# TriggerTrap_MainBoard_0v39_Release.net
KiCad netlist of a schematic drawn in EAGLE
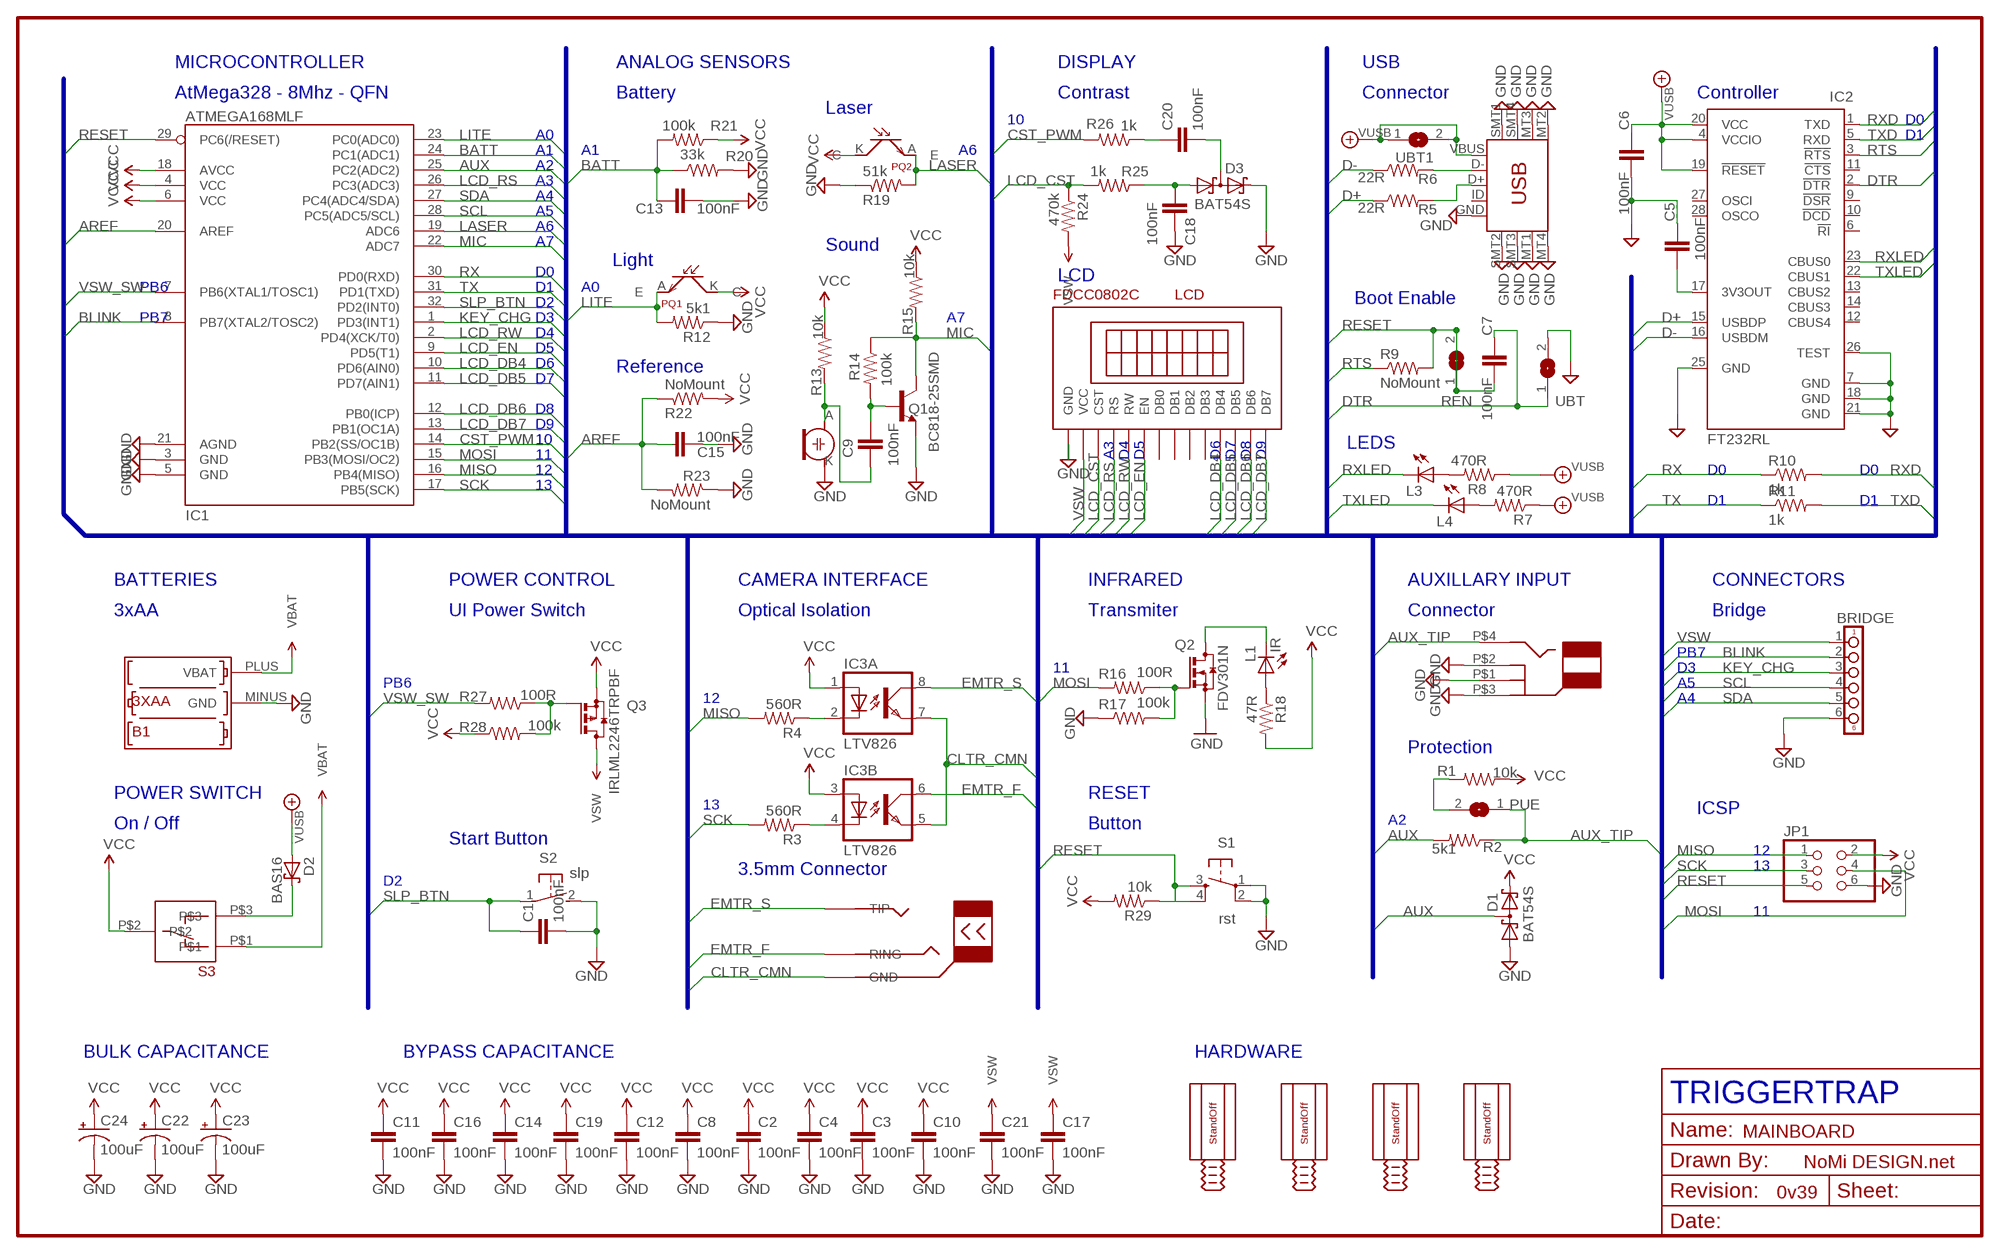
[diagram p0: schematic, sheet 1]

(export (version "E")
  (design (tool "Eeschema 10.0.6"))
  (components
    (comp (ref "AUXJACK")
      (value "CUI_RCJ-017-RCA")
      (footprint "eagle-import:RCA_CUI_RCJ-017")
      (libsource (lib "eagle-import") (part "CUI_RCJ-017-RCA"))
    )
    (comp (ref "B1")
      (value "3XAA")
      (footprint "eagle-import:3XAA-CASE")
      (libsource (lib "eagle-import") (part "3XAA"))
    )
    (comp (ref "BRIDGE")
      (value "PINHD-1X6")
      (footprint "eagle-import:1X06")
      (libsource (lib "eagle-import") (part "PINHD-1X6"))
    )
    (comp (ref "C1")
      (value "100nF")
      (footprint "eagle-import:0603-CAP")
      (libsource (lib "eagle-import") (part "CAP0603-CAP"))
    )
    (comp (ref "C2")
      (value "100nF")
      (footprint "eagle-import:0603-CAP")
      (libsource (lib "eagle-import") (part "CAP0603-CAP"))
    )
    (comp (ref "C3")
      (value "100nF")
      (footprint "eagle-import:0603-CAP")
      (libsource (lib "eagle-import") (part "CAP0603-CAP"))
    )
    (comp (ref "C4")
      (value "100nF")
      (footprint "eagle-import:0603-CAP")
      (libsource (lib "eagle-import") (part "CAP0603-CAP"))
    )
    (comp (ref "C5")
      (value "100nF")
      (footprint "eagle-import:0603-CAP")
      (libsource (lib "eagle-import") (part "CAP0603-CAP"))
    )
    (comp (ref "C6")
      (value "100nF")
      (footprint "eagle-import:0603-CAP")
      (libsource (lib "eagle-import") (part "CAP0603-CAP"))
    )
    (comp (ref "C7")
      (value "100nF")
      (footprint "eagle-import:0603-CAP")
      (libsource (lib "eagle-import") (part "CAP0603-CAP"))
    )
    (comp (ref "C8")
      (value "100nF")
      (footprint "eagle-import:0603-CAP")
      (libsource (lib "eagle-import") (part "CAP0603-CAP"))
    )
    (comp (ref "C9")
      (value "100nF")
      (footprint "eagle-import:0603-CAP")
      (libsource (lib "eagle-import") (part "CAP0603-CAP"))
    )
    (comp (ref "C10")
      (value "100nF")
      (footprint "eagle-import:0603-CAP")
      (libsource (lib "eagle-import") (part "CAP0603-CAP"))
    )
    (comp (ref "C11")
      (value "100nF")
      (footprint "eagle-import:0603-CAP")
      (libsource (lib "eagle-import") (part "CAP0603-CAP"))
    )
    (comp (ref "C12")
      (value "100nF")
      (footprint "eagle-import:0603-CAP")
      (libsource (lib "eagle-import") (part "CAP0603-CAP"))
    )
    (comp (ref "C13")
      (value "100nF")
      (footprint "eagle-import:0603-CAP")
      (libsource (lib "eagle-import") (part "CAP0603-CAP"))
    )
    (comp (ref "C14")
      (value "100nF")
      (footprint "eagle-import:0603-CAP")
      (libsource (lib "eagle-import") (part "CAP0603-CAP"))
    )
    (comp (ref "C15")
      (value "100nF")
      (footprint "eagle-import:0603-CAP")
      (libsource (lib "eagle-import") (part "CAP0603-CAP"))
    )
    (comp (ref "C16")
      (value "100nF")
      (footprint "eagle-import:0603-CAP")
      (libsource (lib "eagle-import") (part "CAP0603-CAP"))
    )
    (comp (ref "C17")
      (value "100nF")
      (footprint "eagle-import:0603-CAP")
      (libsource (lib "eagle-import") (part "CAP0603-CAP"))
    )
    (comp (ref "C18")
      (value "100nF")
      (footprint "eagle-import:0603-CAP")
      (libsource (lib "eagle-import") (part "CAP0603-CAP"))
    )
    (comp (ref "C19")
      (value "100nF")
      (footprint "eagle-import:0603-CAP")
      (libsource (lib "eagle-import") (part "CAP0603-CAP"))
    )
    (comp (ref "C20")
      (value "100nF")
      (footprint "eagle-import:0603-CAP")
      (libsource (lib "eagle-import") (part "CAP0603-CAP"))
    )
    (comp (ref "C21")
      (value "100nF")
      (footprint "eagle-import:0603-CAP")
      (libsource (lib "eagle-import") (part "CAP0603-CAP"))
    )
    (comp (ref "C22")
      (value "100uF")
      (footprint "eagle-import:E2,5-7")
      (libsource (lib "eagle-import") (part "CPOL-USE2.5-7"))
    )
    (comp (ref "C23")
      (value "100uF")
      (footprint "eagle-import:E2,5-7")
      (libsource (lib "eagle-import") (part "CPOL-USE2.5-7"))
    )
    (comp (ref "C24")
      (value "100uF")
      (footprint "eagle-import:E2,5-7")
      (libsource (lib "eagle-import") (part "CPOL-USE2.5-7"))
    )
    (comp (ref "CAMJACK")
      (value "AUDIO_3.5MM_L_3523")
      (footprint "eagle-import:AUDIO_3.5MM_LONG")
      (libsource (lib "eagle-import") (part "AUDIO_3.5MM_L_3523"))
    )
    (comp (ref "D1")
      (value "BAT54S")
      (footprint "eagle-import:SOT23")
      (libsource (lib "eagle-import") (part "BAT54S"))
    )
    (comp (ref "D2")
      (value "BAS16")
      (footprint "eagle-import:SOT23")
      (libsource (lib "eagle-import") (part "BAS40"))
    )
    (comp (ref "D3")
      (value "BAT54S")
      (footprint "eagle-import:SOT23")
      (libsource (lib "eagle-import") (part "BAT54S"))
    )
    (comp (ref "IC1")
      (value "ATMEGA168MLF")
      (footprint "eagle-import:MLF32")
      (libsource (lib "eagle-import") (part "ATMEGA168MLF"))
    )
    (comp (ref "IC2")
      (value "FT232RL")
      (footprint "eagle-import:SSOP28")
      (libsource (lib "eagle-import") (part "FT232RL"))
    )
    (comp (ref "IC3")
      (value "LTV826")
      (footprint "eagle-import:DIL08R")
      (libsource (lib "eagle-import") (part "LTV826"))
    )
    (comp (ref "JP1")
      (value "PINHD-2X3/90")
      (footprint "eagle-import:2X03_90")
      (libsource (lib "eagle-import") (part "PINHD-2X3/90"))
    )
    (comp (ref "L1")
      (value "IR")
      (footprint "eagle-import:SIDE_LED")
      (libsource (lib "eagle-import") (part "LEDSIDE_LED"))
    )
    (comp (ref "L3")
      (value "LEDCHIPLED_0805")
      (footprint "eagle-import:CHIPLED_0805")
      (libsource (lib "eagle-import") (part "LEDCHIPLED_0805"))
    )
    (comp (ref "L4")
      (value "LEDCHIPLED_0805")
      (footprint "eagle-import:CHIPLED_0805")
      (libsource (lib "eagle-import") (part "LEDCHIPLED_0805"))
    )
    (comp (ref "LCD")
      (value "FDCC0802C")
      (footprint "eagle-import:8X2-TOPLCD")
      (libsource (lib "eagle-import") (part "FDCC0802C"))
    )
    (comp (ref "M1")
      (value "254-ECM94-RO")
      (footprint "eagle-import:MIC-254-ECM94-RO")
      (libsource (lib "eagle-import") (part "MIC"))
    )
    (comp (ref "PQ1")
      (value "TEPT4400")
      (footprint "eagle-import:LED-3MM")
      (libsource (lib "eagle-import") (part "AMB-LIGHT-SENS"))
    )
    (comp (ref "PQ2")
      (value "EL-PT204-6C")
      (footprint "eagle-import:LSR-SNS-3MM")
      (libsource (lib "eagle-import") (part "LASER_SNS3MM"))
    )
    (comp (ref "PUE") (value "SJ") (footprint "eagle-import:SJ") (libsource (lib "eagle-import") (part "SJ")))
    (comp (ref "Q1")
      (value "BC818-25SMD")
      (footprint "eagle-import:SOT23-BEC")
      (libsource (lib "eagle-import") (part "BC818SMD-25"))
    )
    (comp (ref "Q2")
      (value "FDV301N")
      (footprint "eagle-import:SOT23")
      (libsource (lib "eagle-import") (part "BSS123"))
    )
    (comp (ref "Q3")
      (value "IRLML2246TRPBF")
      (footprint "eagle-import:SOT23")
      (libsource (lib "eagle-import") (part "BSS84"))
    )
    (comp (ref "R1")
      (value "10k")
      (footprint "eagle-import:0603-RES")
      (libsource (lib "eagle-import") (part "RESISTOR0603-RES"))
    )
    (comp (ref "R2")
      (value "5k1")
      (footprint "eagle-import:0603-RES")
      (libsource (lib "eagle-import") (part "RESISTOR0603-RES"))
    )
    (comp (ref "R3")
      (value "560R")
      (footprint "eagle-import:0603-RES")
      (libsource (lib "eagle-import") (part "RESISTOR0603-RES"))
    )
    (comp (ref "R4")
      (value "560R")
      (footprint "eagle-import:0603-RES")
      (libsource (lib "eagle-import") (part "RESISTOR0603-RES"))
    )
    (comp (ref "R5")
      (value "22R")
      (footprint "eagle-import:R0603")
      (libsource (lib "eagle-import") (part "R-US_R0603"))
    )
    (comp (ref "R6")
      (value "22R")
      (footprint "eagle-import:R0603")
      (libsource (lib "eagle-import") (part "R-US_R0603"))
    )
    (comp (ref "R7")
      (value "470R")
      (footprint "eagle-import:R0603")
      (libsource (lib "eagle-import") (part "R-US_R0603"))
    )
    (comp (ref "R8")
      (value "470R")
      (footprint "eagle-import:R0603")
      (libsource (lib "eagle-import") (part "R-US_R0603"))
    )
    (comp (ref "R9")
      (value "NoMount")
      (footprint "eagle-import:R0603")
      (libsource (lib "eagle-import") (part "R-US_R0603"))
    )
    (comp (ref "R10")
      (value "1k")
      (footprint "eagle-import:R0603")
      (libsource (lib "eagle-import") (part "R-US_R0603"))
    )
    (comp (ref "R11")
      (value "1k")
      (footprint "eagle-import:R0603")
      (libsource (lib "eagle-import") (part "R-US_R0603"))
    )
    (comp (ref "R12")
      (value "5k1")
      (footprint "eagle-import:0603-RES")
      (libsource (lib "eagle-import") (part "RESISTOR0603-RES"))
    )
    (comp (ref "R13")
      (value "10k")
      (footprint "eagle-import:R0603")
      (libsource (lib "eagle-import") (part "R-US_R0603"))
    )
    (comp (ref "R14")
      (value "100k")
      (footprint "eagle-import:R0603")
      (libsource (lib "eagle-import") (part "R-US_R0603"))
    )
    (comp (ref "R15")
      (value "10k")
      (footprint "eagle-import:R0603")
      (libsource (lib "eagle-import") (part "R-US_R0603"))
    )
    (comp (ref "R16")
      (value "100R")
      (footprint "eagle-import:R0603")
      (libsource (lib "eagle-import") (part "R-US_R0603"))
    )
    (comp (ref "R17")
      (value "100k")
      (footprint "eagle-import:R0603")
      (libsource (lib "eagle-import") (part "R-US_R0603"))
    )
    (comp (ref "R18")
      (value "47R")
      (footprint "eagle-import:0603-RES")
      (libsource (lib "eagle-import") (part "RESISTOR0603-RES"))
    )
    (comp (ref "R19")
      (value "51k")
      (footprint "eagle-import:0603-RES")
      (libsource (lib "eagle-import") (part "RESISTOR0603-RES"))
    )
    (comp (ref "R20")
      (value "33k")
      (footprint "eagle-import:R0603")
      (libsource (lib "eagle-import") (part "R-US_R0603"))
    )
    (comp (ref "R21")
      (value "100k")
      (footprint "eagle-import:R0603")
      (libsource (lib "eagle-import") (part "R-US_R0603"))
    )
    (comp (ref "R22")
      (value "NoMount")
      (footprint "eagle-import:R0603")
      (libsource (lib "eagle-import") (part "R-US_R0603"))
    )
    (comp (ref "R23")
      (value "NoMount")
      (footprint "eagle-import:R0603")
      (libsource (lib "eagle-import") (part "R-US_R0603"))
    )
    (comp (ref "R24")
      (value "470k")
      (footprint "eagle-import:R0603")
      (libsource (lib "eagle-import") (part "R-US_R0603"))
    )
    (comp (ref "R25")
      (value "1k")
      (footprint "eagle-import:R0603")
      (libsource (lib "eagle-import") (part "R-US_R0603"))
    )
    (comp (ref "R26")
      (value "1k")
      (footprint "eagle-import:R0603")
      (libsource (lib "eagle-import") (part "R-US_R0603"))
    )
    (comp (ref "R27")
      (value "100R")
      (footprint "eagle-import:R0603")
      (libsource (lib "eagle-import") (part "R-US_R0603"))
    )
    (comp (ref "R28")
      (value "100k")
      (footprint "eagle-import:R0603")
      (libsource (lib "eagle-import") (part "R-US_R0603"))
    )
    (comp (ref "R29")
      (value "10k")
      (footprint "eagle-import:0603-RES")
      (libsource (lib "eagle-import") (part "RESISTOR0603-RES"))
    )
    (comp (ref "REN") (value "SJ") (footprint "eagle-import:SJ") (libsource (lib "eagle-import") (part "SJ")))
    (comp (ref "S1")
      (value "rst")
      (footprint "eagle-import:TACTILE_SWITCH_SMD")
      (libsource (lib "eagle-import") (part "TAC_SWITCHSMD"))
    )
    (comp (ref "S2")
      (value "slp")
      (footprint "eagle-import:B3F-31XX")
      (libsource (lib "eagle-import") (part "31-XX"))
    )
    (comp (ref "S3")
      (value "OS102011MA1QN1")
      (footprint "eagle-import:OS102011MA1QN1")
      (libsource (lib "eagle-import") (part "SLIDESWITCH"))
    )
    (comp (ref "U$2")
      (value "STAND-0FF-3.2")
      (footprint "eagle-import:STAND-OFF")
      (libsource (lib "eagle-import") (part "STAND-0FF-3.2"))
    )
    (comp (ref "U$23")
      (value "STAND-0FF-3.2")
      (footprint "eagle-import:STAND-OFF")
      (libsource (lib "eagle-import") (part "STAND-0FF-3.2"))
    )
    (comp (ref "U$24")
      (value "STAND-0FF-3.2")
      (footprint "eagle-import:STAND-OFF")
      (libsource (lib "eagle-import") (part "STAND-0FF-3.2"))
    )
    (comp (ref "U$25")
      (value "STAND-0FF-3.2")
      (footprint "eagle-import:STAND-OFF")
      (libsource (lib "eagle-import") (part "STAND-0FF-3.2"))
    )
    (comp (ref "UBT") (value "SJ") (footprint "eagle-import:SJ") (libsource (lib "eagle-import") (part "SJ")))
    (comp (ref "UBT1")
      (value "SJ")
      (footprint "eagle-import:SJ")
      (libsource (lib "eagle-import") (part "SJ"))
    )
    (comp (ref "USB")
      (value "USB-MICRO-B-SMD")
      (footprint "eagle-import:USB-MICROB-SMD")
      (libsource (lib "eagle-import") (part "USB-MICRO-B-SMD"))
    )
  )
  (nets
    (net (code "1") (name "/AREF") (class "Default")
      (node (ref "C15") (pin "1") (pinfunction "1_1") (pintype "passive"))
      (node (ref "IC1") (pin "20") (pinfunction "AREF_20") (pintype "bidirectional"))
      (node (ref "R22") (pin "1") (pinfunction "1_1") (pintype "passive"))
      (node (ref "R23") (pin "2") (pinfunction "2_2") (pintype "passive"))
    )
    (net (code "2") (name "/AUX") (class "Default")
      (node (ref "D1") (pin "3") (pinfunction "C1A2_3") (pintype "passive"))
      (node (ref "IC1") (pin "25") (pinfunction "PC2(ADC2)_25") (pintype "bidirectional"))
      (node (ref "R2") (pin "2") (pinfunction "2_2") (pintype "passive"))
    )
    (net (code "3") (name "/AUX_TIP") (class "Default")
      (node (ref "AUXJACK") (pin "P$4") (pinfunction "TIP_P$4") (pintype "bidirectional"))
      (node (ref "PUE") (pin "1") (pinfunction "1_1") (pintype "passive"))
      (node (ref "R2") (pin "1") (pinfunction "1_1") (pintype "passive"))
    )
    (net (code "4") (name "/BATT") (class "Default")
      (node (ref "C13") (pin "1") (pinfunction "1_1") (pintype "passive"))
      (node (ref "IC1") (pin "24") (pinfunction "PC1(ADC1)_24") (pintype "bidirectional"))
      (node (ref "R20") (pin "1") (pinfunction "1_1") (pintype "passive"))
      (node (ref "R21") (pin "2") (pinfunction "2_2") (pintype "passive"))
    )
    (net (code "5") (name "/BLINK") (class "Default")
      (node (ref "BRIDGE") (pin "2") (pinfunction "2_2") (pintype "passive"))
      (node (ref "IC1") (pin "8") (pinfunction "PB7(XTAL2/TOSC2)_8") (pintype "bidirectional"))
    )
    (net (code "6") (name "/CLTR_CMN") (class "Default")
      (node (ref "CAMJACK") (pin "P$1") (pinfunction "GND_P$1") (pintype "bidirectional"))
      (node (ref "IC3") (pin "5") (pinfunction "EMIT_5") (pintype "passive"))
      (node (ref "IC3") (pin "7") (pinfunction "EMIT_7") (pintype "passive"))
    )
    (net (code "7") (name "/CST_PWM") (class "Default")
      (node (ref "IC1") (pin "14") (pinfunction "PB2(SS/OC1B)_14") (pintype "bidirectional"))
      (node (ref "R26") (pin "2") (pinfunction "2_2") (pintype "passive"))
    )
    (net (code "8") (name "/D+") (class "Default")
      (node (ref "IC2") (pin "15") (pinfunction "USBDP_15") (pintype "bidirectional"))
      (node (ref "R5") (pin "1") (pinfunction "1_1") (pintype "passive"))
    )
    (net (code "9") (name "/D-") (class "Default")
      (node (ref "IC2") (pin "16") (pinfunction "USBDM_16") (pintype "bidirectional"))
      (node (ref "R6") (pin "1") (pinfunction "1_1") (pintype "passive"))
    )
    (net (code "10") (name "/DTR") (class "Default")
      (node (ref "C7") (pin "1") (pinfunction "1_1") (pintype "passive"))
      (node (ref "IC2") (pin "2") (pinfunction "~{DTR}_2") (pintype "output"))
      (node (ref "UBT") (pin "1") (pinfunction "1_1") (pintype "passive"))
    )
    (net (code "11") (name "/EMTR_F") (class "Default")
      (node (ref "CAMJACK") (pin "P$3") (pinfunction "RING_P$3") (pintype "bidirectional"))
      (node (ref "IC3") (pin "6") (pinfunction "COL_6") (pintype "passive"))
    )
    (net (code "12") (name "/EMTR_S") (class "Default")
      (node (ref "CAMJACK") (pin "P$2") (pinfunction "TIP_P$2") (pintype "bidirectional"))
      (node (ref "IC3") (pin "8") (pinfunction "COL_8") (pintype "passive"))
    )
    (net (code "13") (name "/KEY_CHG") (class "Default")
      (node (ref "BRIDGE") (pin "3") (pinfunction "3_3") (pintype "passive"))
      (node (ref "IC1") (pin "1") (pinfunction "PD3(INT1)_1") (pintype "bidirectional"))
    )
    (net (code "14") (name "/LASER") (class "Default")
      (node (ref "IC1") (pin "19") (pinfunction "ADC6_19") (pintype "bidirectional"))
      (node (ref "PQ2") (pin "A") (pinfunction "E_A") (pintype "bidirectional"))
      (node (ref "R19") (pin "2") (pinfunction "2_2") (pintype "passive"))
    )
    (net (code "15") (name "/LCD_CST") (class "Default")
      (node (ref "LCD") (pin "P$3") (pinfunction "CST_P$3") (pintype "bidirectional"))
      (node (ref "R24") (pin "1") (pinfunction "1_1") (pintype "passive"))
      (node (ref "R25") (pin "2") (pinfunction "2_2") (pintype "passive"))
    )
    (net (code "16") (name "/LCD_DB4") (class "Default")
      (node (ref "IC1") (pin "10") (pinfunction "PD6(AIN0)_10") (pintype "bidirectional"))
      (node (ref "LCD") (pin "P$11") (pinfunction "DB4_P$11") (pintype "bidirectional"))
    )
    (net (code "17") (name "/LCD_DB5") (class "Default")
      (node (ref "IC1") (pin "11") (pinfunction "PD7(AIN1)_11") (pintype "bidirectional"))
      (node (ref "LCD") (pin "P$12") (pinfunction "DB5_P$12") (pintype "bidirectional"))
    )
    (net (code "18") (name "/LCD_DB6") (class "Default")
      (node (ref "IC1") (pin "12") (pinfunction "PB0(ICP)_12") (pintype "bidirectional"))
      (node (ref "LCD") (pin "P$13") (pinfunction "DB6_P$13") (pintype "bidirectional"))
    )
    (net (code "19") (name "/LCD_DB7") (class "Default")
      (node (ref "IC1") (pin "13") (pinfunction "PB1(OC1A)_13") (pintype "bidirectional"))
      (node (ref "LCD") (pin "P$14") (pinfunction "DB7_P$14") (pintype "bidirectional"))
    )
    (net (code "20") (name "/LCD_EN") (class "Default")
      (node (ref "IC1") (pin "9") (pinfunction "PD5(T1)_9") (pintype "bidirectional"))
      (node (ref "LCD") (pin "P$6") (pinfunction "EN_P$6") (pintype "bidirectional"))
    )
    (net (code "21") (name "/LCD_RS") (class "Default")
      (node (ref "IC1") (pin "26") (pinfunction "PC3(ADC3)_26") (pintype "bidirectional"))
      (node (ref "LCD") (pin "P$4") (pinfunction "RS_P$4") (pintype "bidirectional"))
    )
    (net (code "22") (name "/LCD_RW") (class "Default")
      (node (ref "IC1") (pin "2") (pinfunction "PD4(XCK/T0)_2") (pintype "bidirectional"))
      (node (ref "LCD") (pin "P$5") (pinfunction "RW_P$5") (pintype "bidirectional"))
    )
    (net (code "23") (name "/LITE") (class "Default")
      (node (ref "IC1") (pin "23") (pinfunction "PC0(ADC0)_23") (pintype "bidirectional"))
      (node (ref "PQ1") (pin "A") (pinfunction "E_A") (pintype "bidirectional"))
      (node (ref "R12") (pin "2") (pinfunction "2_2") (pintype "passive"))
    )
    (net (code "24") (name "/MIC") (class "Default")
      (node (ref "IC1") (pin "22") (pinfunction "ADC7_22") (pintype "bidirectional"))
      (node (ref "Q1") (pin "C") (pinfunction "C_C") (pintype "passive"))
      (node (ref "R14") (pin "1") (pinfunction "1_1") (pintype "passive"))
      (node (ref "R15") (pin "2") (pinfunction "2_2") (pintype "passive"))
    )
    (net (code "25") (name "/MISO") (class "Default")
      (node (ref "IC1") (pin "16") (pinfunction "PB4(MISO)_16") (pintype "bidirectional"))
      (node (ref "JP1") (pin "1") (pinfunction "1_1") (pintype "passive"))
      (node (ref "R4") (pin "2") (pinfunction "2_2") (pintype "passive"))
    )
    (net (code "26") (name "/MOSI") (class "Default")
      (node (ref "IC1") (pin "15") (pinfunction "PB3(MOSI/OC2)_15") (pintype "bidirectional"))
      (node (ref "JP1") (pin "4") (pinfunction "4_4") (pintype "passive"))
      (node (ref "R16") (pin "2") (pinfunction "2_2") (pintype "passive"))
    )
    (net (code "27") (name "/RESET") (class "Default")
      (node (ref "C7") (pin "2") (pinfunction "2_2") (pintype "passive"))
      (node (ref "IC1") (pin "29") (pinfunction "PC6(/RESET)_29") (pintype "bidirectional"))
      (node (ref "JP1") (pin "5") (pinfunction "5_5") (pintype "passive"))
      (node (ref "R29") (pin "1") (pinfunction "1_1") (pintype "passive"))
      (node (ref "R9") (pin "2") (pinfunction "2_2") (pintype "passive"))
      (node (ref "REN") (pin "1") (pinfunction "1_1") (pintype "passive"))
      (node (ref "REN") (pin "2") (pinfunction "2_2") (pintype "passive"))
      (node (ref "S1") (pin "3") (pinfunction "3_3") (pintype "passive"))
      (node (ref "S1") (pin "4") (pinfunction "4_4") (pintype "passive"))
    )
    (net (code "28") (name "/RTS") (class "Default")
      (node (ref "IC2") (pin "3") (pinfunction "~{RTS}_3") (pintype "output"))
      (node (ref "R9") (pin "1") (pinfunction "1_1") (pintype "passive"))
    )
    (net (code "29") (name "/RX") (class "Default")
      (node (ref "IC1") (pin "30") (pinfunction "PD0(RXD)_30") (pintype "bidirectional"))
      (node (ref "R10") (pin "1") (pinfunction "1_1") (pintype "passive"))
    )
    (net (code "30") (name "/RXD") (class "Default")
      (node (ref "IC2") (pin "1") (pinfunction "TXD_1") (pintype "output"))
      (node (ref "R10") (pin "2") (pinfunction "2_2") (pintype "passive"))
    )
    (net (code "31") (name "/RXLED") (class "Default")
      (node (ref "IC2") (pin "23") (pinfunction "CBUS0_23") (pintype "bidirectional"))
      (node (ref "L3") (pin "C") (pinfunction "C_C") (pintype "passive"))
    )
    (net (code "32") (name "/SCK") (class "Default")
      (node (ref "IC1") (pin "17") (pinfunction "PB5(SCK)_17") (pintype "bidirectional"))
      (node (ref "JP1") (pin "3") (pinfunction "3_3") (pintype "passive"))
      (node (ref "R3") (pin "2") (pinfunction "2_2") (pintype "passive"))
    )
    (net (code "33") (name "/SCL") (class "Default")
      (node (ref "BRIDGE") (pin "4") (pinfunction "4_4") (pintype "passive"))
      (node (ref "IC1") (pin "28") (pinfunction "PC5(ADC5/SCL)_28") (pintype "bidirectional"))
    )
    (net (code "34") (name "/SDA") (class "Default")
      (node (ref "BRIDGE") (pin "5") (pinfunction "5_5") (pintype "passive"))
      (node (ref "IC1") (pin "27") (pinfunction "PC4(ADC4/SDA)_27") (pintype "bidirectional"))
    )
    (net (code "35") (name "/SLP_BTN") (class "Default")
      (node (ref "C1") (pin "1") (pinfunction "1_1") (pintype "passive"))
      (node (ref "IC1") (pin "32") (pinfunction "PD2(INT0)_32") (pintype "bidirectional"))
      (node (ref "S2") (pin "1") (pinfunction "P_1") (pintype "passive"))
    )
    (net (code "36") (name "/TX") (class "Default")
      (node (ref "IC1") (pin "31") (pinfunction "PD1(TXD)_31") (pintype "bidirectional"))
      (node (ref "R11") (pin "1") (pinfunction "1_1") (pintype "passive"))
    )
    (net (code "37") (name "/TXD") (class "Default")
      (node (ref "IC2") (pin "5") (pinfunction "RXD_5") (pintype "input"))
      (node (ref "R11") (pin "2") (pinfunction "2_2") (pintype "passive"))
    )
    (net (code "38") (name "/TXLED") (class "Default")
      (node (ref "IC2") (pin "22") (pinfunction "CBUS1_22") (pintype "bidirectional"))
      (node (ref "L4") (pin "C") (pinfunction "C_C") (pintype "passive"))
    )
    (net (code "39") (name "/VSW_SW") (class "Default")
      (node (ref "IC1") (pin "7") (pinfunction "PB6(XTAL1/TOSC1)_7") (pintype "bidirectional"))
      (node (ref "R27") (pin "2") (pinfunction "2_2") (pintype "passive"))
    )
    (net (code "40") (name "GND") (class "Default")
      (node (ref "AUXJACK") (pin "P$1") (pinfunction "GND1_P$1") (pintype "bidirectional"))
      (node (ref "AUXJACK") (pin "P$2") (pinfunction "GND2_P$2") (pintype "bidirectional"))
      (node (ref "AUXJACK") (pin "P$3") (pinfunction "GND_P$3") (pintype "bidirectional"))
      (node (ref "B1") (pin "MINUS") (pinfunction "GND_MINUS") (pintype "bidirectional"))
      (node (ref "BRIDGE") (pin "6") (pinfunction "6_6") (pintype "passive"))
      (node (ref "C1") (pin "2") (pinfunction "2_2") (pintype "passive"))
      (node (ref "C10") (pin "2") (pinfunction "2_2") (pintype "passive"))
      (node (ref "C11") (pin "2") (pinfunction "2_2") (pintype "passive"))
      (node (ref "C12") (pin "2") (pinfunction "2_2") (pintype "passive"))
      (node (ref "C13") (pin "2") (pinfunction "2_2") (pintype "passive"))
      (node (ref "C14") (pin "2") (pinfunction "2_2") (pintype "passive"))
      (node (ref "C15") (pin "2") (pinfunction "2_2") (pintype "passive"))
      (node (ref "C16") (pin "2") (pinfunction "2_2") (pintype "passive"))
      (node (ref "C17") (pin "2") (pinfunction "2_2") (pintype "passive"))
      (node (ref "C18") (pin "1") (pinfunction "1_1") (pintype "passive"))
      (node (ref "C19") (pin "2") (pinfunction "2_2") (pintype "passive"))
      (node (ref "C2") (pin "2") (pinfunction "2_2") (pintype "passive"))
      (node (ref "C21") (pin "2") (pinfunction "2_2") (pintype "passive"))
      (node (ref "C22") (pin "-") (pinfunction "-_-") (pintype "passive"))
      (node (ref "C23") (pin "-") (pinfunction "-_-") (pintype "passive"))
      (node (ref "C24") (pin "-") (pinfunction "-_-") (pintype "passive"))
      (node (ref "C3") (pin "2") (pinfunction "2_2") (pintype "passive"))
      (node (ref "C4") (pin "2") (pinfunction "2_2") (pintype "passive"))
      (node (ref "C5") (pin "1") (pinfunction "1_1") (pintype "passive"))
      (node (ref "C6") (pin "2") (pinfunction "2_2") (pintype "passive"))
      (node (ref "C8") (pin "2") (pinfunction "2_2") (pintype "passive"))
      (node (ref "D1") (pin "1") (pinfunction "A1_1") (pintype "passive"))
      (node (ref "D3") (pin "2") (pinfunction "C2_2") (pintype "passive"))
      (node (ref "IC1") (pin "21") (pinfunction "AGND_21") (pintype "bidirectional"))
      (node (ref "IC1") (pin "3") (pinfunction "GND_3") (pintype "bidirectional"))
      (node (ref "IC1") (pin "5") (pinfunction "GND_5") (pintype "bidirectional"))
      (node (ref "IC2") (pin "18") (pinfunction "GND_18") (pintype "power_in"))
      (node (ref "IC2") (pin "21") (pinfunction "GND_21") (pintype "power_in"))
      (node (ref "IC2") (pin "25") (pinfunction "GND_25") (pintype "power_in"))
      (node (ref "IC2") (pin "26") (pinfunction "TEST_26") (pintype "input"))
      (node (ref "IC2") (pin "7") (pinfunction "GND_7") (pintype "power_in"))
      (node (ref "JP1") (pin "6") (pinfunction "6_6") (pintype "passive"))
      (node (ref "LCD") (pin "P$1") (pinfunction "GND_P$1") (pintype "bidirectional"))
      (node (ref "M1") (pin "K") (pinfunction "K_K") (pintype "passive"))
      (node (ref "Q1") (pin "E") (pinfunction "E_E") (pintype "passive"))
      (node (ref "Q2") (pin "2") (pinfunction "S_2") (pintype "passive"))
      (node (ref "R12") (pin "1") (pinfunction "1_1") (pintype "passive"))
      (node (ref "R17") (pin "1") (pinfunction "1_1") (pintype "passive"))
      (node (ref "R19") (pin "1") (pinfunction "1_1") (pintype "passive"))
      (node (ref "R20") (pin "2") (pinfunction "2_2") (pintype "passive"))
      (node (ref "R23") (pin "1") (pinfunction "1_1") (pintype "passive"))
      (node (ref "S1") (pin "1") (pinfunction "1_1") (pintype "passive"))
      (node (ref "S1") (pin "2") (pinfunction "2_2") (pintype "passive"))
      (node (ref "S2") (pin "2") (pinfunction "S_2") (pintype "passive"))
      (node (ref "UBT") (pin "2") (pinfunction "2_2") (pintype "passive"))
      (node (ref "USB") (pin "GND") (pinfunction "GND_GND") (pintype "bidirectional"))
      (node (ref "USB") (pin "MT1") (pinfunction "MTN1_MT1") (pintype "bidirectional"))
      (node (ref "USB") (pin "MT2") (pinfunction "MTN2_MT2") (pintype "bidirectional"))
      (node (ref "USB") (pin "MT3") (pinfunction "MTN3_MT3") (pintype "bidirectional"))
      (node (ref "USB") (pin "MT4") (pinfunction "MTN4_MT4") (pintype "bidirectional"))
      (node (ref "USB") (pin "SMT1") (pinfunction "SMT1_SMT1") (pintype "bidirectional"))
      (node (ref "USB") (pin "SMT2") (pinfunction "SMT2_SMT2") (pintype "bidirectional"))
      (node (ref "USB") (pin "SMT3") (pinfunction "SMT3_SMT3") (pintype "bidirectional"))
      (node (ref "USB") (pin "SMT4") (pinfunction "SMT4_SMT4") (pintype "bidirectional"))
    )
    (net (code "41") (name "Net-(C9-Pad1)") (class "Default")
      (node (ref "C9") (pin "1") (pinfunction "1_1") (pintype "passive"))
      (node (ref "M1") (pin "A") (pinfunction "A_A") (pintype "passive"))
      (node (ref "R13") (pin "2") (pinfunction "2_2") (pintype "passive"))
    )
    (net (code "42") (name "Net-(C9-Pad2)") (class "Default")
      (node (ref "C9") (pin "2") (pinfunction "2_2") (pintype "passive"))
      (node (ref "Q1") (pin "B") (pinfunction "B_B") (pintype "passive"))
      (node (ref "R14") (pin "2") (pinfunction "2_2") (pintype "passive"))
    )
    (net (code "43") (name "Net-(C20-Pad1)") (class "Default")
      (node (ref "C20") (pin "1") (pinfunction "1_1") (pintype "passive"))
      (node (ref "R26") (pin "1") (pinfunction "1_1") (pintype "passive"))
    )
    (net (code "44") (name "Net-(D2-C)") (class "Default")
      (node (ref "D2") (pin "3") (pinfunction "C_3") (pintype "passive"))
      (node (ref "S3") (pin "P$3") (pinfunction "P$3_P$3") (pintype "bidirectional"))
    )
    (net (code "45") (name "Net-(D3-A1)") (class "Default")
      (node (ref "C18") (pin "2") (pinfunction "2_2") (pintype "passive"))
      (node (ref "D3") (pin "1") (pinfunction "A1_1") (pintype "passive"))
      (node (ref "R25") (pin "1") (pinfunction "1_1") (pintype "passive"))
    )
    (net (code "46") (name "Net-(D3-C1A2)") (class "Default")
      (node (ref "C20") (pin "2") (pinfunction "2_2") (pintype "passive"))
      (node (ref "D3") (pin "3") (pinfunction "C1A2_3") (pintype "passive"))
    )
    (net (code "47") (name "Net-(IC2-3V3OUT)") (class "Default")
      (node (ref "C5") (pin "2") (pinfunction "2_2") (pintype "passive"))
      (node (ref "IC2") (pin "17") (pinfunction "3V3OUT_17") (pintype "output"))
    )
    (net (code "48") (name "Net-(IC3A-C)") (class "Default")
      (node (ref "IC3") (pin "2") (pinfunction "C_2") (pintype "passive"))
      (node (ref "R4") (pin "1") (pinfunction "1_1") (pintype "passive"))
    )
    (net (code "49") (name "Net-(IC3B-C)") (class "Default")
      (node (ref "IC3") (pin "4") (pinfunction "C_4") (pintype "passive"))
      (node (ref "R3") (pin "1") (pinfunction "1_1") (pintype "passive"))
    )
    (net (code "50") (name "Net-(L1-C)") (class "Default")
      (node (ref "L1") (pin "K") (pinfunction "C_K") (pintype "passive"))
      (node (ref "Q2") (pin "3") (pinfunction "D_3") (pintype "passive"))
    )
    (net (code "51") (name "Net-(L1-PadA)") (class "Default")
      (node (ref "L1") (pin "A") (pinfunction "A_A") (pintype "passive"))
      (node (ref "R18") (pin "1") (pinfunction "1_1") (pintype "passive"))
    )
    (net (code "52") (name "Net-(L3-PadA)") (class "Default")
      (node (ref "L3") (pin "A") (pinfunction "A_A") (pintype "passive"))
      (node (ref "R8") (pin "2") (pinfunction "2_2") (pintype "passive"))
    )
    (net (code "53") (name "Net-(L4-PadA)") (class "Default")
      (node (ref "L4") (pin "A") (pinfunction "A_A") (pintype "passive"))
      (node (ref "R7") (pin "2") (pinfunction "2_2") (pintype "passive"))
    )
    (net (code "54") (name "Net-(PUE-Pad2)") (class "Default")
      (node (ref "PUE") (pin "2") (pinfunction "2_2") (pintype "passive"))
      (node (ref "R1") (pin "2") (pinfunction "2_2") (pintype "passive"))
    )
    (net (code "55") (name "Net-(Q2-G)") (class "Default")
      (node (ref "Q2") (pin "1") (pinfunction "G_1") (pintype "passive"))
      (node (ref "R16") (pin "1") (pinfunction "1_1") (pintype "passive"))
      (node (ref "R17") (pin "2") (pinfunction "2_2") (pintype "passive"))
    )
    (net (code "56") (name "Net-(Q3-G)") (class "Default")
      (node (ref "Q3") (pin "1") (pinfunction "G_1") (pintype "passive"))
      (node (ref "R27") (pin "1") (pinfunction "1_1") (pintype "passive"))
      (node (ref "R28") (pin "2") (pinfunction "2_2") (pintype "passive"))
    )
    (net (code "57") (name "Net-(R5-Pad2)") (class "Default")
      (node (ref "R5") (pin "2") (pinfunction "2_2") (pintype "passive"))
      (node (ref "USB") (pin "D+") (pinfunction "D+_D+") (pintype "bidirectional"))
    )
    (net (code "58") (name "Net-(R6-Pad2)") (class "Default")
      (node (ref "R6") (pin "2") (pinfunction "2_2") (pintype "passive"))
      (node (ref "USB") (pin "D-") (pinfunction "D-_D-") (pintype "bidirectional"))
    )
    (net (code "59") (name "VBAT") (class "Default")
      (node (ref "B1") (pin "PLUS") (pinfunction "VBAT_PLUS") (pintype "bidirectional"))
      (node (ref "S3") (pin "P$1") (pinfunction "P$1_P$1") (pintype "bidirectional"))
    )
    (net (code "60") (name "VCC") (class "Default")
      (node (ref "C10") (pin "1") (pinfunction "1_1") (pintype "passive"))
      (node (ref "C11") (pin "1") (pinfunction "1_1") (pintype "passive"))
      (node (ref "C12") (pin "1") (pinfunction "1_1") (pintype "passive"))
      (node (ref "C14") (pin "1") (pinfunction "1_1") (pintype "passive"))
      (node (ref "C16") (pin "1") (pinfunction "1_1") (pintype "passive"))
      (node (ref "C19") (pin "1") (pinfunction "1_1") (pintype "passive"))
      (node (ref "C2") (pin "1") (pinfunction "1_1") (pintype "passive"))
      (node (ref "C22") (pin "+") (pinfunction "+_+") (pintype "passive"))
      (node (ref "C23") (pin "+") (pinfunction "+_+") (pintype "passive"))
      (node (ref "C24") (pin "+") (pinfunction "+_+") (pintype "passive"))
      (node (ref "C3") (pin "1") (pinfunction "1_1") (pintype "passive"))
      (node (ref "C4") (pin "1") (pinfunction "1_1") (pintype "passive"))
      (node (ref "C8") (pin "1") (pinfunction "1_1") (pintype "passive"))
      (node (ref "D1") (pin "2") (pinfunction "C2_2") (pintype "passive"))
      (node (ref "IC1") (pin "18") (pinfunction "AVCC_18") (pintype "bidirectional"))
      (node (ref "IC1") (pin "4") (pinfunction "VCC_4") (pintype "bidirectional"))
      (node (ref "IC1") (pin "6") (pinfunction "VCC_6") (pintype "bidirectional"))
      (node (ref "IC3") (pin "1") (pinfunction "A_1") (pintype "passive"))
      (node (ref "IC3") (pin "3") (pinfunction "A_3") (pintype "passive"))
      (node (ref "JP1") (pin "2") (pinfunction "2_2") (pintype "passive"))
      (node (ref "PQ1") (pin "K") (pinfunction "C_K") (pintype "bidirectional"))
      (node (ref "PQ2") (pin "K") (pinfunction "C_K") (pintype "bidirectional"))
      (node (ref "Q3") (pin "2") (pinfunction "S_2") (pintype "passive"))
      (node (ref "R1") (pin "1") (pinfunction "1_1") (pintype "passive"))
      (node (ref "R13") (pin "1") (pinfunction "1_1") (pintype "passive"))
      (node (ref "R15") (pin "1") (pinfunction "1_1") (pintype "passive"))
      (node (ref "R18") (pin "2") (pinfunction "2_2") (pintype "passive"))
      (node (ref "R21") (pin "1") (pinfunction "1_1") (pintype "passive"))
      (node (ref "R22") (pin "2") (pinfunction "2_2") (pintype "passive"))
      (node (ref "R28") (pin "1") (pinfunction "1_1") (pintype "passive"))
      (node (ref "R29") (pin "2") (pinfunction "2_2") (pintype "passive"))
      (node (ref "S3") (pin "P$2") (pinfunction "P$2_P$2") (pintype "bidirectional"))
    )
    (net (code "61") (name "VSW") (class "Default")
      (node (ref "BRIDGE") (pin "1") (pinfunction "1_1") (pintype "passive"))
      (node (ref "C17") (pin "1") (pinfunction "1_1") (pintype "passive"))
      (node (ref "C21") (pin "1") (pinfunction "1_1") (pintype "passive"))
      (node (ref "LCD") (pin "P$2") (pinfunction "VCC_P$2") (pintype "bidirectional"))
      (node (ref "Q3") (pin "3") (pinfunction "D_3") (pintype "passive"))
      (node (ref "R24") (pin "2") (pinfunction "2_2") (pintype "passive"))
    )
    (net (code "62") (name "VUSB") (class "Default")
      (node (ref "C6") (pin "1") (pinfunction "1_1") (pintype "passive"))
      (node (ref "D2") (pin "1") (pinfunction "A_1") (pintype "passive"))
      (node (ref "IC2") (pin "19") (pinfunction "~{RESET}_19") (pintype "input"))
      (node (ref "IC2") (pin "20") (pinfunction "VCC_20") (pintype "power_in"))
      (node (ref "IC2") (pin "4") (pinfunction "VCCIO_4") (pintype "power_in"))
      (node (ref "R7") (pin "1") (pinfunction "1_1") (pintype "passive"))
      (node (ref "R8") (pin "1") (pinfunction "1_1") (pintype "passive"))
      (node (ref "UBT1") (pin "1") (pinfunction "1_1") (pintype "passive"))
      (node (ref "UBT1") (pin "2") (pinfunction "2_2") (pintype "passive"))
      (node (ref "USB") (pin "VBUS") (pinfunction "VBUS_VBUS") (pintype "bidirectional"))
    )
    (net (code "63") (name "unconnected-(IC2-CBUS2-Pad13)") (class "Default")
      (node (ref "IC2") (pin "13") (pinfunction "CBUS2_13") (pintype "bidirectional"))
    )
    (net (code "64") (name "unconnected-(IC2-CBUS3-Pad14)") (class "Default")
      (node (ref "IC2") (pin "14") (pinfunction "CBUS3_14") (pintype "bidirectional"))
    )
    (net (code "65") (name "unconnected-(IC2-CBUS4-Pad12)") (class "Default")
      (node (ref "IC2") (pin "12") (pinfunction "CBUS4_12") (pintype "bidirectional"))
    )
    (net (code "66") (name "unconnected-(IC2-OSCI-Pad27)") (class "Default")
      (node (ref "IC2") (pin "27") (pinfunction "OSCI_27") (pintype "input"))
    )
    (net (code "67") (name "unconnected-(IC2-OSCO-Pad28)") (class "Default")
      (node (ref "IC2") (pin "28") (pinfunction "OSCO_28") (pintype "output"))
    )
    (net (code "68") (name "unconnected-(IC2-~{CTS}-Pad11)") (class "Default")
      (node (ref "IC2") (pin "11") (pinfunction "~{CTS}_11") (pintype "input"))
    )
    (net (code "69") (name "unconnected-(IC2-~{DCD}-Pad10)") (class "Default")
      (node (ref "IC2") (pin "10") (pinfunction "~{DCD}_10") (pintype "input"))
    )
    (net (code "70") (name "unconnected-(IC2-~{DSR}-Pad9)") (class "Default")
      (node (ref "IC2") (pin "9") (pinfunction "~{DSR}_9") (pintype "input"))
    )
    (net (code "71") (name "unconnected-(IC2-~{RI}-Pad6)") (class "Default")
      (node (ref "IC2") (pin "6") (pinfunction "~{RI}_6") (pintype "input"))
    )
    (net (code "72") (name "unconnected-(LCD-DB0-PadP$7)") (class "Default")
      (node (ref "LCD") (pin "P$7") (pinfunction "DB0_P$7") (pintype "bidirectional"))
    )
    (net (code "73") (name "unconnected-(LCD-DB1-PadP$8)") (class "Default")
      (node (ref "LCD") (pin "P$8") (pinfunction "DB1_P$8") (pintype "bidirectional"))
    )
    (net (code "74") (name "unconnected-(LCD-DB2-PadP$9)") (class "Default")
      (node (ref "LCD") (pin "P$9") (pinfunction "DB2_P$9") (pintype "bidirectional"))
    )
    (net (code "75") (name "unconnected-(LCD-DB3-PadP$10)") (class "Default")
      (node (ref "LCD") (pin "P$10") (pinfunction "DB3_P$10") (pintype "bidirectional"))
    )
    (net (code "76") (name "unconnected-(USB-PadID)") (class "Default")
      (node (ref "USB") (pin "ID") (pinfunction "ID_ID") (pintype "bidirectional"))
    )
  )
)
